# Logic_Port.net
KiCad netlist of a schematic drawn in Altium Designer
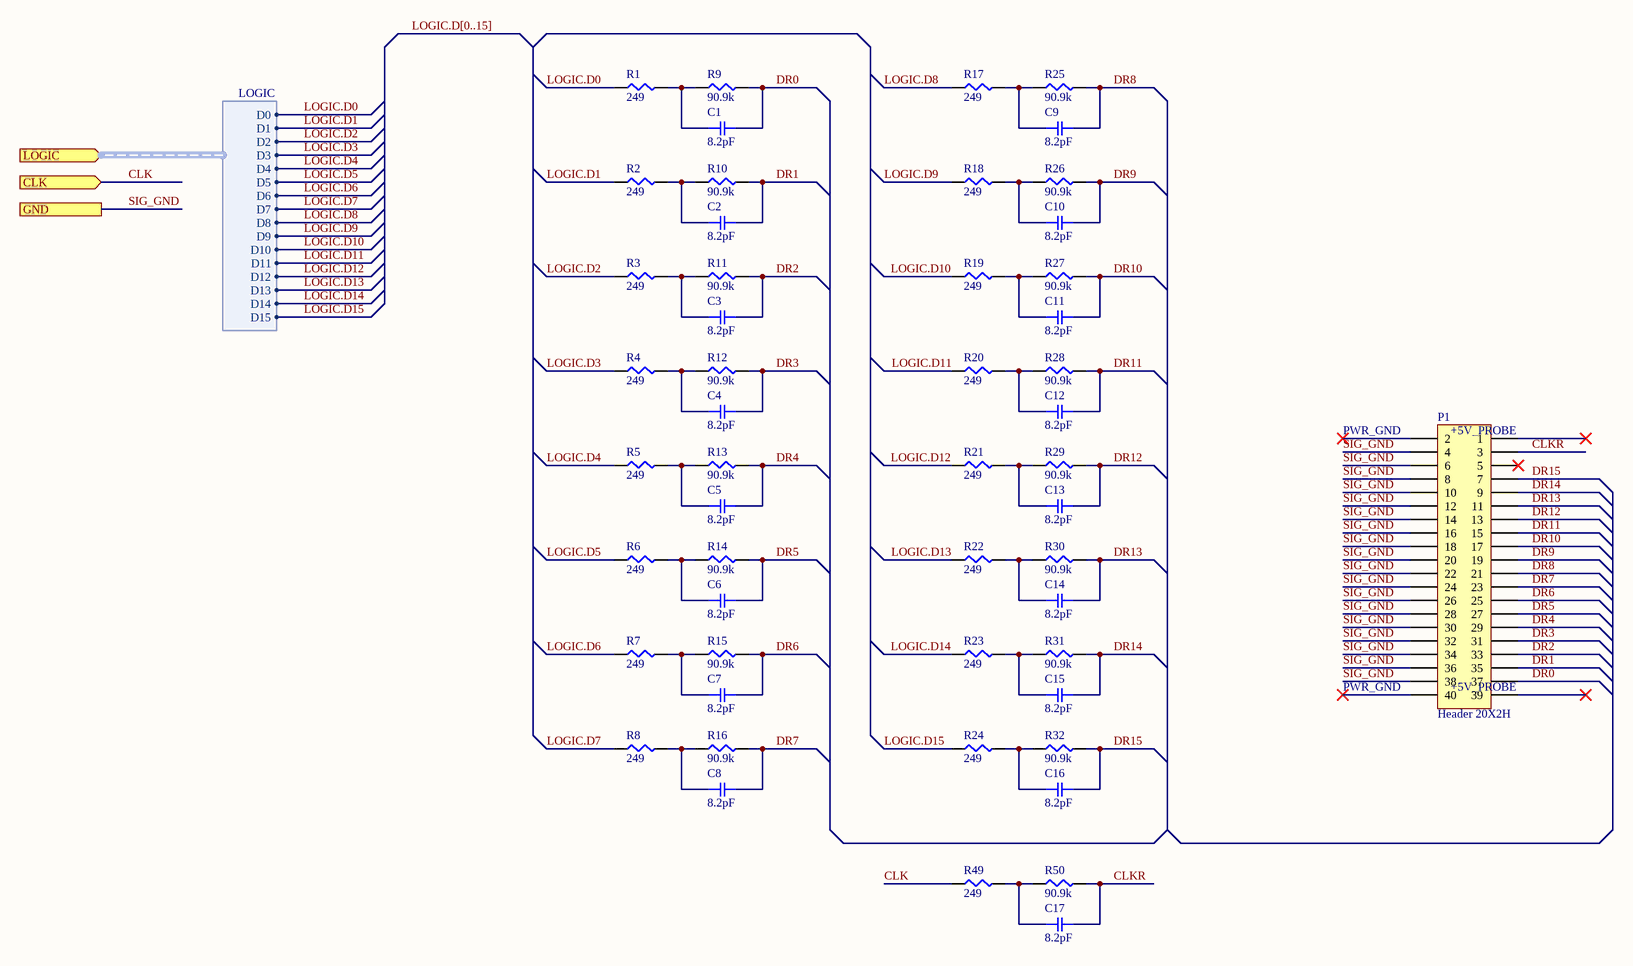
[diagram p0: Logic Port.SchDoc]

(export (version "E")
  (design (tool "Eeschema 10.0.6"))
  (components
    (comp (ref "C1")
      (value "8.2pF")
      (footprint "SMD-0603C")
      (description "CAP CER 8.2PF 50V NP0 0603")
      (fields
        (field (name "DIGI-KEY PART NUMBER") "490-12727-1-ND")
        (field (name "PART NUMBER") "GRM1885C1H8R2BA01D")
      )
      (libsource (lib "capacitor_murata_0603") (part "GRM1885C1H8R2BA01D"))
    )
    (comp (ref "C2")
      (value "8.2pF")
      (footprint "SMD-0603C")
      (description "CAP CER 8.2PF 50V NP0 0603")
      (fields
        (field (name "DIGI-KEY PART NUMBER") "490-12727-1-ND")
        (field (name "PART NUMBER") "GRM1885C1H8R2BA01D")
      )
      (libsource (lib "capacitor_murata_0603") (part "GRM1885C1H8R2BA01D"))
    )
    (comp (ref "C3")
      (value "8.2pF")
      (footprint "SMD-0603C")
      (description "CAP CER 8.2PF 50V NP0 0603")
      (fields
        (field (name "DIGI-KEY PART NUMBER") "490-12727-1-ND")
        (field (name "PART NUMBER") "GRM1885C1H8R2BA01D")
      )
      (libsource (lib "capacitor_murata_0603") (part "GRM1885C1H8R2BA01D"))
    )
    (comp (ref "C4")
      (value "8.2pF")
      (footprint "SMD-0603C")
      (description "CAP CER 8.2PF 50V NP0 0603")
      (fields
        (field (name "DIGI-KEY PART NUMBER") "490-12727-1-ND")
        (field (name "PART NUMBER") "GRM1885C1H8R2BA01D")
      )
      (libsource (lib "capacitor_murata_0603") (part "GRM1885C1H8R2BA01D"))
    )
    (comp (ref "C5")
      (value "8.2pF")
      (footprint "SMD-0603C")
      (description "CAP CER 8.2PF 50V NP0 0603")
      (fields
        (field (name "DIGI-KEY PART NUMBER") "490-12727-1-ND")
        (field (name "PART NUMBER") "GRM1885C1H8R2BA01D")
      )
      (libsource (lib "capacitor_murata_0603") (part "GRM1885C1H8R2BA01D"))
    )
    (comp (ref "C6")
      (value "8.2pF")
      (footprint "SMD-0603C")
      (description "CAP CER 8.2PF 50V NP0 0603")
      (fields
        (field (name "DIGI-KEY PART NUMBER") "490-12727-1-ND")
        (field (name "PART NUMBER") "GRM1885C1H8R2BA01D")
      )
      (libsource (lib "capacitor_murata_0603") (part "GRM1885C1H8R2BA01D"))
    )
    (comp (ref "C7")
      (value "8.2pF")
      (footprint "SMD-0603C")
      (description "CAP CER 8.2PF 50V NP0 0603")
      (fields
        (field (name "DIGI-KEY PART NUMBER") "490-12727-1-ND")
        (field (name "PART NUMBER") "GRM1885C1H8R2BA01D")
      )
      (libsource (lib "capacitor_murata_0603") (part "GRM1885C1H8R2BA01D"))
    )
    (comp (ref "C8")
      (value "8.2pF")
      (footprint "SMD-0603C")
      (description "CAP CER 8.2PF 50V NP0 0603")
      (fields
        (field (name "DIGI-KEY PART NUMBER") "490-12727-1-ND")
        (field (name "PART NUMBER") "GRM1885C1H8R2BA01D")
      )
      (libsource (lib "capacitor_murata_0603") (part "GRM1885C1H8R2BA01D"))
    )
    (comp (ref "C9")
      (value "8.2pF")
      (footprint "SMD-0603C")
      (description "CAP CER 8.2PF 50V NP0 0603")
      (fields
        (field (name "DIGI-KEY PART NUMBER") "490-12727-1-ND")
        (field (name "PART NUMBER") "GRM1885C1H8R2BA01D")
      )
      (libsource (lib "capacitor_murata_0603") (part "GRM1885C1H8R2BA01D"))
    )
    (comp (ref "C10")
      (value "8.2pF")
      (footprint "SMD-0603C")
      (description "CAP CER 8.2PF 50V NP0 0603")
      (fields
        (field (name "DIGI-KEY PART NUMBER") "490-12727-1-ND")
        (field (name "PART NUMBER") "GRM1885C1H8R2BA01D")
      )
      (libsource (lib "capacitor_murata_0603") (part "GRM1885C1H8R2BA01D"))
    )
    (comp (ref "C11")
      (value "8.2pF")
      (footprint "SMD-0603C")
      (description "CAP CER 8.2PF 50V NP0 0603")
      (fields
        (field (name "DIGI-KEY PART NUMBER") "490-12727-1-ND")
        (field (name "PART NUMBER") "GRM1885C1H8R2BA01D")
      )
      (libsource (lib "capacitor_murata_0603") (part "GRM1885C1H8R2BA01D"))
    )
    (comp (ref "C12")
      (value "8.2pF")
      (footprint "SMD-0603C")
      (description "CAP CER 8.2PF 50V NP0 0603")
      (fields
        (field (name "DIGI-KEY PART NUMBER") "490-12727-1-ND")
        (field (name "PART NUMBER") "GRM1885C1H8R2BA01D")
      )
      (libsource (lib "capacitor_murata_0603") (part "GRM1885C1H8R2BA01D"))
    )
    (comp (ref "C13")
      (value "8.2pF")
      (footprint "SMD-0603C")
      (description "CAP CER 8.2PF 50V NP0 0603")
      (fields
        (field (name "DIGI-KEY PART NUMBER") "490-12727-1-ND")
        (field (name "PART NUMBER") "GRM1885C1H8R2BA01D")
      )
      (libsource (lib "capacitor_murata_0603") (part "GRM1885C1H8R2BA01D"))
    )
    (comp (ref "C14")
      (value "8.2pF")
      (footprint "SMD-0603C")
      (description "CAP CER 8.2PF 50V NP0 0603")
      (fields
        (field (name "DIGI-KEY PART NUMBER") "490-12727-1-ND")
        (field (name "PART NUMBER") "GRM1885C1H8R2BA01D")
      )
      (libsource (lib "capacitor_murata_0603") (part "GRM1885C1H8R2BA01D"))
    )
    (comp (ref "C15")
      (value "8.2pF")
      (footprint "SMD-0603C")
      (description "CAP CER 8.2PF 50V NP0 0603")
      (fields
        (field (name "DIGI-KEY PART NUMBER") "490-12727-1-ND")
        (field (name "PART NUMBER") "GRM1885C1H8R2BA01D")
      )
      (libsource (lib "capacitor_murata_0603") (part "GRM1885C1H8R2BA01D"))
    )
    (comp (ref "C16")
      (value "8.2pF")
      (footprint "SMD-0603C")
      (description "CAP CER 8.2PF 50V NP0 0603")
      (fields
        (field (name "DIGI-KEY PART NUMBER") "490-12727-1-ND")
        (field (name "PART NUMBER") "GRM1885C1H8R2BA01D")
      )
      (libsource (lib "capacitor_murata_0603") (part "GRM1885C1H8R2BA01D"))
    )
    (comp (ref "C17")
      (value "8.2pF")
      (footprint "SMD-0603C")
      (description "CAP CER 8.2PF 50V NP0 0603")
      (fields
        (field (name "DIGI-KEY PART NUMBER") "490-12727-1-ND")
        (field (name "PART NUMBER") "GRM1885C1H8R2BA01D")
      )
      (libsource (lib "capacitor_murata_0603") (part "GRM1885C1H8R2BA01D"))
    )
    (comp (ref "P1")
      (value "Header 20X2H")
      (footprint "HDR2X20H")
      (description "Header, 20-Pin, Dual row, Right Angle")
      (fields (field (name "PUBLISHER") "Altium Limited"))
      (libsource (lib "Miscellaneous Connectors") (part "Header 20X2H"))
    )
    (comp (ref "R1")
      (value "249")
      (footprint "SMD-0603-RES")
      (description "RES SMD 249 OHM 1% 1/10W 0603")
      (fields (field (name "PART NUMBER") "ERJ-3EKF2490V") (field (name "DIGI-KEY PART NUMBER") "P249HCT-ND"))
      (libsource (lib "Panasonic_ERJ_0603") (part "ERJ-3EKF2490V"))
    )
    (comp (ref "R2")
      (value "249")
      (footprint "SMD-0603-RES")
      (description "RES SMD 249 OHM 1% 1/10W 0603")
      (fields (field (name "PART NUMBER") "ERJ-3EKF2490V") (field (name "DIGI-KEY PART NUMBER") "P249HCT-ND"))
      (libsource (lib "Panasonic_ERJ_0603") (part "ERJ-3EKF2490V"))
    )
    (comp (ref "R3")
      (value "249")
      (footprint "SMD-0603-RES")
      (description "RES SMD 249 OHM 1% 1/10W 0603")
      (fields (field (name "PART NUMBER") "ERJ-3EKF2490V") (field (name "DIGI-KEY PART NUMBER") "P249HCT-ND"))
      (libsource (lib "Panasonic_ERJ_0603") (part "ERJ-3EKF2490V"))
    )
    (comp (ref "R4")
      (value "249")
      (footprint "SMD-0603-RES")
      (description "RES SMD 249 OHM 1% 1/10W 0603")
      (fields (field (name "PART NUMBER") "ERJ-3EKF2490V") (field (name "DIGI-KEY PART NUMBER") "P249HCT-ND"))
      (libsource (lib "Panasonic_ERJ_0603") (part "ERJ-3EKF2490V"))
    )
    (comp (ref "R5")
      (value "249")
      (footprint "SMD-0603-RES")
      (description "RES SMD 249 OHM 1% 1/10W 0603")
      (fields (field (name "PART NUMBER") "ERJ-3EKF2490V") (field (name "DIGI-KEY PART NUMBER") "P249HCT-ND"))
      (libsource (lib "Panasonic_ERJ_0603") (part "ERJ-3EKF2490V"))
    )
    (comp (ref "R6")
      (value "249")
      (footprint "SMD-0603-RES")
      (description "RES SMD 249 OHM 1% 1/10W 0603")
      (fields (field (name "PART NUMBER") "ERJ-3EKF2490V") (field (name "DIGI-KEY PART NUMBER") "P249HCT-ND"))
      (libsource (lib "Panasonic_ERJ_0603") (part "ERJ-3EKF2490V"))
    )
    (comp (ref "R7")
      (value "249")
      (footprint "SMD-0603-RES")
      (description "RES SMD 249 OHM 1% 1/10W 0603")
      (fields (field (name "PART NUMBER") "ERJ-3EKF2490V") (field (name "DIGI-KEY PART NUMBER") "P249HCT-ND"))
      (libsource (lib "Panasonic_ERJ_0603") (part "ERJ-3EKF2490V"))
    )
    (comp (ref "R8")
      (value "249")
      (footprint "SMD-0603-RES")
      (description "RES SMD 249 OHM 1% 1/10W 0603")
      (fields (field (name "PART NUMBER") "ERJ-3EKF2490V") (field (name "DIGI-KEY PART NUMBER") "P249HCT-ND"))
      (libsource (lib "Panasonic_ERJ_0603") (part "ERJ-3EKF2490V"))
    )
    (comp (ref "R9")
      (value "90.9k")
      (footprint "SMD-0603-RES")
      (description "RES SMD 90.9K OHM 1% 1/10W 0603")
      (fields
        (field (name "PART NUMBER") "ERJ-3EKF9092V")
        (field (name "DIGI-KEY PART NUMBER") "P90.9KHCT-ND")
      )
      (libsource (lib "Panasonic_ERJ_0603") (part "ERJ-3EKF9092V"))
    )
    (comp (ref "R10")
      (value "90.9k")
      (footprint "SMD-0603-RES")
      (description "RES SMD 90.9K OHM 1% 1/10W 0603")
      (fields
        (field (name "PART NUMBER") "ERJ-3EKF9092V")
        (field (name "DIGI-KEY PART NUMBER") "P90.9KHCT-ND")
      )
      (libsource (lib "Panasonic_ERJ_0603") (part "ERJ-3EKF9092V"))
    )
    (comp (ref "R11")
      (value "90.9k")
      (footprint "SMD-0603-RES")
      (description "RES SMD 90.9K OHM 1% 1/10W 0603")
      (fields
        (field (name "PART NUMBER") "ERJ-3EKF9092V")
        (field (name "DIGI-KEY PART NUMBER") "P90.9KHCT-ND")
      )
      (libsource (lib "Panasonic_ERJ_0603") (part "ERJ-3EKF9092V"))
    )
    (comp (ref "R12")
      (value "90.9k")
      (footprint "SMD-0603-RES")
      (description "RES SMD 90.9K OHM 1% 1/10W 0603")
      (fields
        (field (name "PART NUMBER") "ERJ-3EKF9092V")
        (field (name "DIGI-KEY PART NUMBER") "P90.9KHCT-ND")
      )
      (libsource (lib "Panasonic_ERJ_0603") (part "ERJ-3EKF9092V"))
    )
    (comp (ref "R13")
      (value "90.9k")
      (footprint "SMD-0603-RES")
      (description "RES SMD 90.9K OHM 1% 1/10W 0603")
      (fields
        (field (name "PART NUMBER") "ERJ-3EKF9092V")
        (field (name "DIGI-KEY PART NUMBER") "P90.9KHCT-ND")
      )
      (libsource (lib "Panasonic_ERJ_0603") (part "ERJ-3EKF9092V"))
    )
    (comp (ref "R14")
      (value "90.9k")
      (footprint "SMD-0603-RES")
      (description "RES SMD 90.9K OHM 1% 1/10W 0603")
      (fields
        (field (name "PART NUMBER") "ERJ-3EKF9092V")
        (field (name "DIGI-KEY PART NUMBER") "P90.9KHCT-ND")
      )
      (libsource (lib "Panasonic_ERJ_0603") (part "ERJ-3EKF9092V"))
    )
    (comp (ref "R15")
      (value "90.9k")
      (footprint "SMD-0603-RES")
      (description "RES SMD 90.9K OHM 1% 1/10W 0603")
      (fields
        (field (name "PART NUMBER") "ERJ-3EKF9092V")
        (field (name "DIGI-KEY PART NUMBER") "P90.9KHCT-ND")
      )
      (libsource (lib "Panasonic_ERJ_0603") (part "ERJ-3EKF9092V"))
    )
    (comp (ref "R16")
      (value "90.9k")
      (footprint "SMD-0603-RES")
      (description "RES SMD 90.9K OHM 1% 1/10W 0603")
      (fields
        (field (name "PART NUMBER") "ERJ-3EKF9092V")
        (field (name "DIGI-KEY PART NUMBER") "P90.9KHCT-ND")
      )
      (libsource (lib "Panasonic_ERJ_0603") (part "ERJ-3EKF9092V"))
    )
    (comp (ref "R17")
      (value "249")
      (footprint "SMD-0603-RES")
      (description "RES SMD 249 OHM 1% 1/10W 0603")
      (fields (field (name "PART NUMBER") "ERJ-3EKF2490V") (field (name "DIGI-KEY PART NUMBER") "P249HCT-ND"))
      (libsource (lib "Panasonic_ERJ_0603") (part "ERJ-3EKF2490V"))
    )
    (comp (ref "R18")
      (value "249")
      (footprint "SMD-0603-RES")
      (description "RES SMD 249 OHM 1% 1/10W 0603")
      (fields (field (name "PART NUMBER") "ERJ-3EKF2490V") (field (name "DIGI-KEY PART NUMBER") "P249HCT-ND"))
      (libsource (lib "Panasonic_ERJ_0603") (part "ERJ-3EKF2490V"))
    )
    (comp (ref "R19")
      (value "249")
      (footprint "SMD-0603-RES")
      (description "RES SMD 249 OHM 1% 1/10W 0603")
      (fields (field (name "PART NUMBER") "ERJ-3EKF2490V") (field (name "DIGI-KEY PART NUMBER") "P249HCT-ND"))
      (libsource (lib "Panasonic_ERJ_0603") (part "ERJ-3EKF2490V"))
    )
    (comp (ref "R20")
      (value "249")
      (footprint "SMD-0603-RES")
      (description "RES SMD 249 OHM 1% 1/10W 0603")
      (fields (field (name "PART NUMBER") "ERJ-3EKF2490V") (field (name "DIGI-KEY PART NUMBER") "P249HCT-ND"))
      (libsource (lib "Panasonic_ERJ_0603") (part "ERJ-3EKF2490V"))
    )
    (comp (ref "R21")
      (value "249")
      (footprint "SMD-0603-RES")
      (description "RES SMD 249 OHM 1% 1/10W 0603")
      (fields (field (name "PART NUMBER") "ERJ-3EKF2490V") (field (name "DIGI-KEY PART NUMBER") "P249HCT-ND"))
      (libsource (lib "Panasonic_ERJ_0603") (part "ERJ-3EKF2490V"))
    )
    (comp (ref "R22")
      (value "249")
      (footprint "SMD-0603-RES")
      (description "RES SMD 249 OHM 1% 1/10W 0603")
      (fields (field (name "PART NUMBER") "ERJ-3EKF2490V") (field (name "DIGI-KEY PART NUMBER") "P249HCT-ND"))
      (libsource (lib "Panasonic_ERJ_0603") (part "ERJ-3EKF2490V"))
    )
    (comp (ref "R23")
      (value "249")
      (footprint "SMD-0603-RES")
      (description "RES SMD 249 OHM 1% 1/10W 0603")
      (fields (field (name "PART NUMBER") "ERJ-3EKF2490V") (field (name "DIGI-KEY PART NUMBER") "P249HCT-ND"))
      (libsource (lib "Panasonic_ERJ_0603") (part "ERJ-3EKF2490V"))
    )
    (comp (ref "R24")
      (value "249")
      (footprint "SMD-0603-RES")
      (description "RES SMD 249 OHM 1% 1/10W 0603")
      (fields (field (name "PART NUMBER") "ERJ-3EKF2490V") (field (name "DIGI-KEY PART NUMBER") "P249HCT-ND"))
      (libsource (lib "Panasonic_ERJ_0603") (part "ERJ-3EKF2490V"))
    )
    (comp (ref "R25")
      (value "90.9k")
      (footprint "SMD-0603-RES")
      (description "RES SMD 90.9K OHM 1% 1/10W 0603")
      (fields
        (field (name "PART NUMBER") "ERJ-3EKF9092V")
        (field (name "DIGI-KEY PART NUMBER") "P90.9KHCT-ND")
      )
      (libsource (lib "Panasonic_ERJ_0603") (part "ERJ-3EKF9092V"))
    )
    (comp (ref "R26")
      (value "90.9k")
      (footprint "SMD-0603-RES")
      (description "RES SMD 90.9K OHM 1% 1/10W 0603")
      (fields
        (field (name "PART NUMBER") "ERJ-3EKF9092V")
        (field (name "DIGI-KEY PART NUMBER") "P90.9KHCT-ND")
      )
      (libsource (lib "Panasonic_ERJ_0603") (part "ERJ-3EKF9092V"))
    )
    (comp (ref "R27")
      (value "90.9k")
      (footprint "SMD-0603-RES")
      (description "RES SMD 90.9K OHM 1% 1/10W 0603")
      (fields
        (field (name "PART NUMBER") "ERJ-3EKF9092V")
        (field (name "DIGI-KEY PART NUMBER") "P90.9KHCT-ND")
      )
      (libsource (lib "Panasonic_ERJ_0603") (part "ERJ-3EKF9092V"))
    )
    (comp (ref "R28")
      (value "90.9k")
      (footprint "SMD-0603-RES")
      (description "RES SMD 90.9K OHM 1% 1/10W 0603")
      (fields
        (field (name "PART NUMBER") "ERJ-3EKF9092V")
        (field (name "DIGI-KEY PART NUMBER") "P90.9KHCT-ND")
      )
      (libsource (lib "Panasonic_ERJ_0603") (part "ERJ-3EKF9092V"))
    )
    (comp (ref "R29")
      (value "90.9k")
      (footprint "SMD-0603-RES")
      (description "RES SMD 90.9K OHM 1% 1/10W 0603")
      (fields
        (field (name "PART NUMBER") "ERJ-3EKF9092V")
        (field (name "DIGI-KEY PART NUMBER") "P90.9KHCT-ND")
      )
      (libsource (lib "Panasonic_ERJ_0603") (part "ERJ-3EKF9092V"))
    )
    (comp (ref "R30")
      (value "90.9k")
      (footprint "SMD-0603-RES")
      (description "RES SMD 90.9K OHM 1% 1/10W 0603")
      (fields
        (field (name "PART NUMBER") "ERJ-3EKF9092V")
        (field (name "DIGI-KEY PART NUMBER") "P90.9KHCT-ND")
      )
      (libsource (lib "Panasonic_ERJ_0603") (part "ERJ-3EKF9092V"))
    )
    (comp (ref "R31")
      (value "90.9k")
      (footprint "SMD-0603-RES")
      (description "RES SMD 90.9K OHM 1% 1/10W 0603")
      (fields
        (field (name "PART NUMBER") "ERJ-3EKF9092V")
        (field (name "DIGI-KEY PART NUMBER") "P90.9KHCT-ND")
      )
      (libsource (lib "Panasonic_ERJ_0603") (part "ERJ-3EKF9092V"))
    )
    (comp (ref "R32")
      (value "90.9k")
      (footprint "SMD-0603-RES")
      (description "RES SMD 90.9K OHM 1% 1/10W 0603")
      (fields
        (field (name "PART NUMBER") "ERJ-3EKF9092V")
        (field (name "DIGI-KEY PART NUMBER") "P90.9KHCT-ND")
      )
      (libsource (lib "Panasonic_ERJ_0603") (part "ERJ-3EKF9092V"))
    )
    (comp (ref "R49")
      (value "249")
      (footprint "SMD-0603-RES")
      (description "RES SMD 249 OHM 1% 1/10W 0603")
      (fields (field (name "PART NUMBER") "ERJ-3EKF2490V") (field (name "DIGI-KEY PART NUMBER") "P249HCT-ND"))
      (libsource (lib "Panasonic_ERJ_0603") (part "ERJ-3EKF2490V"))
    )
    (comp (ref "R50")
      (value "90.9k")
      (footprint "SMD-0603-RES")
      (description "RES SMD 90.9K OHM 1% 1/10W 0603")
      (fields
        (field (name "PART NUMBER") "ERJ-3EKF9092V")
        (field (name "DIGI-KEY PART NUMBER") "P90.9KHCT-ND")
      )
      (libsource (lib "Panasonic_ERJ_0603") (part "ERJ-3EKF9092V"))
    )
  )
  (nets
    (net (code "2") (name "/CLK") (class "Default")
      (node (ref "R49") (pin "1") (pinfunction "1_1") (pintype "passive"))
    )
    (net (code "3") (name "/CLKR") (class "Default")
      (node (ref "C17") (pin "2") (pinfunction "2_2") (pintype "passive"))
      (node (ref "P1") (pin "3") (pinfunction "3_3") (pintype "passive"))
      (node (ref "R50") (pin "2") (pinfunction "2_2") (pintype "passive"))
    )
    (net (code "4") (name "/DR0") (class "Default")
      (node (ref "C1") (pin "2") (pinfunction "2_2") (pintype "passive"))
      (node (ref "P1") (pin "37") (pinfunction "37_37") (pintype "passive"))
      (node (ref "R9") (pin "2") (pinfunction "2_2") (pintype "passive"))
    )
    (net (code "5") (name "/DR1") (class "Default")
      (node (ref "C2") (pin "2") (pinfunction "2_2") (pintype "passive"))
      (node (ref "P1") (pin "35") (pinfunction "35_35") (pintype "passive"))
      (node (ref "R10") (pin "2") (pinfunction "2_2") (pintype "passive"))
    )
    (net (code "6") (name "/DR2") (class "Default")
      (node (ref "C3") (pin "2") (pinfunction "2_2") (pintype "passive"))
      (node (ref "P1") (pin "33") (pinfunction "33_33") (pintype "passive"))
      (node (ref "R11") (pin "2") (pinfunction "2_2") (pintype "passive"))
    )
    (net (code "7") (name "/DR3") (class "Default")
      (node (ref "C4") (pin "2") (pinfunction "2_2") (pintype "passive"))
      (node (ref "P1") (pin "31") (pinfunction "31_31") (pintype "passive"))
      (node (ref "R12") (pin "2") (pinfunction "2_2") (pintype "passive"))
    )
    (net (code "8") (name "/DR4") (class "Default")
      (node (ref "C5") (pin "2") (pinfunction "2_2") (pintype "passive"))
      (node (ref "P1") (pin "29") (pinfunction "29_29") (pintype "passive"))
      (node (ref "R13") (pin "2") (pinfunction "2_2") (pintype "passive"))
    )
    (net (code "9") (name "/DR5") (class "Default")
      (node (ref "C6") (pin "2") (pinfunction "2_2") (pintype "passive"))
      (node (ref "P1") (pin "27") (pinfunction "27_27") (pintype "passive"))
      (node (ref "R14") (pin "2") (pinfunction "2_2") (pintype "passive"))
    )
    (net (code "10") (name "/DR6") (class "Default")
      (node (ref "C7") (pin "2") (pinfunction "2_2") (pintype "passive"))
      (node (ref "P1") (pin "25") (pinfunction "25_25") (pintype "passive"))
      (node (ref "R15") (pin "2") (pinfunction "2_2") (pintype "passive"))
    )
    (net (code "11") (name "/DR7") (class "Default")
      (node (ref "C8") (pin "2") (pinfunction "2_2") (pintype "passive"))
      (node (ref "P1") (pin "23") (pinfunction "23_23") (pintype "passive"))
      (node (ref "R16") (pin "2") (pinfunction "2_2") (pintype "passive"))
    )
    (net (code "12") (name "/DR8") (class "Default")
      (node (ref "C9") (pin "2") (pinfunction "2_2") (pintype "passive"))
      (node (ref "P1") (pin "21") (pinfunction "21_21") (pintype "passive"))
      (node (ref "R25") (pin "2") (pinfunction "2_2") (pintype "passive"))
    )
    (net (code "13") (name "/DR9") (class "Default")
      (node (ref "C10") (pin "2") (pinfunction "2_2") (pintype "passive"))
      (node (ref "P1") (pin "19") (pinfunction "19_19") (pintype "passive"))
      (node (ref "R26") (pin "2") (pinfunction "2_2") (pintype "passive"))
    )
    (net (code "14") (name "/DR10") (class "Default")
      (node (ref "C11") (pin "2") (pinfunction "2_2") (pintype "passive"))
      (node (ref "P1") (pin "17") (pinfunction "17_17") (pintype "passive"))
      (node (ref "R27") (pin "2") (pinfunction "2_2") (pintype "passive"))
    )
    (net (code "15") (name "/DR11") (class "Default")
      (node (ref "C12") (pin "2") (pinfunction "2_2") (pintype "passive"))
      (node (ref "P1") (pin "15") (pinfunction "15_15") (pintype "passive"))
      (node (ref "R28") (pin "2") (pinfunction "2_2") (pintype "passive"))
    )
    (net (code "16") (name "/DR12") (class "Default")
      (node (ref "C13") (pin "2") (pinfunction "2_2") (pintype "passive"))
      (node (ref "P1") (pin "13") (pinfunction "13_13") (pintype "passive"))
      (node (ref "R29") (pin "2") (pinfunction "2_2") (pintype "passive"))
    )
    (net (code "17") (name "/DR13") (class "Default")
      (node (ref "C14") (pin "2") (pinfunction "2_2") (pintype "passive"))
      (node (ref "P1") (pin "11") (pinfunction "11_11") (pintype "passive"))
      (node (ref "R30") (pin "2") (pinfunction "2_2") (pintype "passive"))
    )
    (net (code "18") (name "/DR14") (class "Default")
      (node (ref "C15") (pin "2") (pinfunction "2_2") (pintype "passive"))
      (node (ref "P1") (pin "9") (pinfunction "9_9") (pintype "passive"))
      (node (ref "R31") (pin "2") (pinfunction "2_2") (pintype "passive"))
    )
    (net (code "19") (name "/DR15") (class "Default")
      (node (ref "C16") (pin "2") (pinfunction "2_2") (pintype "passive"))
      (node (ref "P1") (pin "7") (pinfunction "7_7") (pintype "passive"))
      (node (ref "R32") (pin "2") (pinfunction "2_2") (pintype "passive"))
    )
    (net (code "20") (name "/LOGIC.D0") (class "Default")
      (node (ref "R1") (pin "1") (pinfunction "1_1") (pintype "passive"))
    )
    (net (code "21") (name "/LOGIC.D1") (class "Default")
      (node (ref "R2") (pin "1") (pinfunction "1_1") (pintype "passive"))
    )
    (net (code "22") (name "/LOGIC.D2") (class "Default")
      (node (ref "R3") (pin "1") (pinfunction "1_1") (pintype "passive"))
    )
    (net (code "23") (name "/LOGIC.D3") (class "Default")
      (node (ref "R4") (pin "1") (pinfunction "1_1") (pintype "passive"))
    )
    (net (code "24") (name "/LOGIC.D4") (class "Default")
      (node (ref "R5") (pin "1") (pinfunction "1_1") (pintype "passive"))
    )
    (net (code "25") (name "/LOGIC.D5") (class "Default")
      (node (ref "R6") (pin "1") (pinfunction "1_1") (pintype "passive"))
    )
    (net (code "26") (name "/LOGIC.D6") (class "Default")
      (node (ref "R7") (pin "1") (pinfunction "1_1") (pintype "passive"))
    )
    (net (code "27") (name "/LOGIC.D7") (class "Default")
      (node (ref "R8") (pin "1") (pinfunction "1_1") (pintype "passive"))
    )
    (net (code "28") (name "/LOGIC.D8") (class "Default")
      (node (ref "R17") (pin "1") (pinfunction "1_1") (pintype "passive"))
    )
    (net (code "29") (name "/LOGIC.D9") (class "Default")
      (node (ref "R18") (pin "1") (pinfunction "1_1") (pintype "passive"))
    )
    (net (code "30") (name "/LOGIC.D10") (class "Default")
      (node (ref "R19") (pin "1") (pinfunction "1_1") (pintype "passive"))
    )
    (net (code "31") (name "/LOGIC.D11") (class "Default")
      (node (ref "R20") (pin "1") (pinfunction "1_1") (pintype "passive"))
    )
    (net (code "32") (name "/LOGIC.D12") (class "Default")
      (node (ref "R21") (pin "1") (pinfunction "1_1") (pintype "passive"))
    )
    (net (code "33") (name "/LOGIC.D13") (class "Default")
      (node (ref "R22") (pin "1") (pinfunction "1_1") (pintype "passive"))
    )
    (net (code "34") (name "/LOGIC.D14") (class "Default")
      (node (ref "R23") (pin "1") (pinfunction "1_1") (pintype "passive"))
    )
    (net (code "35") (name "/LOGIC.D15") (class "Default")
      (node (ref "R24") (pin "1") (pinfunction "1_1") (pintype "passive"))
    )
    (net (code "37") (name "/SIG_GND") (class "Default")
      (node (ref "P1") (pin "10") (pinfunction "10_10") (pintype "passive"))
      (node (ref "P1") (pin "12") (pinfunction "12_12") (pintype "passive"))
      (node (ref "P1") (pin "14") (pinfunction "14_14") (pintype "passive"))
      (node (ref "P1") (pin "16") (pinfunction "16_16") (pintype "passive"))
      (node (ref "P1") (pin "18") (pinfunction "18_18") (pintype "passive"))
      (node (ref "P1") (pin "20") (pinfunction "20_20") (pintype "passive"))
      (node (ref "P1") (pin "22") (pinfunction "22_22") (pintype "passive"))
      (node (ref "P1") (pin "24") (pinfunction "24_24") (pintype "passive"))
      (node (ref "P1") (pin "26") (pinfunction "26_26") (pintype "passive"))
      (node (ref "P1") (pin "28") (pinfunction "28_28") (pintype "passive"))
      (node (ref "P1") (pin "30") (pinfunction "30_30") (pintype "passive"))
      (node (ref "P1") (pin "32") (pinfunction "32_32") (pintype "passive"))
      (node (ref "P1") (pin "34") (pinfunction "34_34") (pintype "passive"))
      (node (ref "P1") (pin "36") (pinfunction "36_36") (pintype "passive"))
      (node (ref "P1") (pin "38") (pinfunction "38_38") (pintype "passive"))
      (node (ref "P1") (pin "4") (pinfunction "4_4") (pintype "passive"))
      (node (ref "P1") (pin "6") (pinfunction "6_6") (pintype "passive"))
      (node (ref "P1") (pin "8") (pinfunction "8_8") (pintype "passive"))
    )
    (net (code "39") (name "Net-(C1-Pad1)") (class "Default")
      (node (ref "C1") (pin "1") (pinfunction "1_1") (pintype "passive"))
      (node (ref "R1") (pin "2") (pinfunction "2_2") (pintype "passive"))
      (node (ref "R9") (pin "1") (pinfunction "1_1") (pintype "passive"))
    )
    (net (code "40") (name "Net-(C2-Pad1)") (class "Default")
      (node (ref "C2") (pin "1") (pinfunction "1_1") (pintype "passive"))
      (node (ref "R10") (pin "1") (pinfunction "1_1") (pintype "passive"))
      (node (ref "R2") (pin "2") (pinfunction "2_2") (pintype "passive"))
    )
    (net (code "41") (name "Net-(C3-Pad1)") (class "Default")
      (node (ref "C3") (pin "1") (pinfunction "1_1") (pintype "passive"))
      (node (ref "R11") (pin "1") (pinfunction "1_1") (pintype "passive"))
      (node (ref "R3") (pin "2") (pinfunction "2_2") (pintype "passive"))
    )
    (net (code "42") (name "Net-(C4-Pad1)") (class "Default")
      (node (ref "C4") (pin "1") (pinfunction "1_1") (pintype "passive"))
      (node (ref "R12") (pin "1") (pinfunction "1_1") (pintype "passive"))
      (node (ref "R4") (pin "2") (pinfunction "2_2") (pintype "passive"))
    )
    (net (code "43") (name "Net-(C5-Pad1)") (class "Default")
      (node (ref "C5") (pin "1") (pinfunction "1_1") (pintype "passive"))
      (node (ref "R13") (pin "1") (pinfunction "1_1") (pintype "passive"))
      (node (ref "R5") (pin "2") (pinfunction "2_2") (pintype "passive"))
    )
    (net (code "44") (name "Net-(C6-Pad1)") (class "Default")
      (node (ref "C6") (pin "1") (pinfunction "1_1") (pintype "passive"))
      (node (ref "R14") (pin "1") (pinfunction "1_1") (pintype "passive"))
      (node (ref "R6") (pin "2") (pinfunction "2_2") (pintype "passive"))
    )
    (net (code "45") (name "Net-(C7-Pad1)") (class "Default")
      (node (ref "C7") (pin "1") (pinfunction "1_1") (pintype "passive"))
      (node (ref "R15") (pin "1") (pinfunction "1_1") (pintype "passive"))
      (node (ref "R7") (pin "2") (pinfunction "2_2") (pintype "passive"))
    )
    (net (code "46") (name "Net-(C8-Pad1)") (class "Default")
      (node (ref "C8") (pin "1") (pinfunction "1_1") (pintype "passive"))
      (node (ref "R16") (pin "1") (pinfunction "1_1") (pintype "passive"))
      (node (ref "R8") (pin "2") (pinfunction "2_2") (pintype "passive"))
    )
    (net (code "47") (name "Net-(C9-Pad1)") (class "Default")
      (node (ref "C9") (pin "1") (pinfunction "1_1") (pintype "passive"))
      (node (ref "R17") (pin "2") (pinfunction "2_2") (pintype "passive"))
      (node (ref "R25") (pin "1") (pinfunction "1_1") (pintype "passive"))
    )
    (net (code "48") (name "Net-(C10-Pad1)") (class "Default")
      (node (ref "C10") (pin "1") (pinfunction "1_1") (pintype "passive"))
      (node (ref "R18") (pin "2") (pinfunction "2_2") (pintype "passive"))
      (node (ref "R26") (pin "1") (pinfunction "1_1") (pintype "passive"))
    )
    (net (code "49") (name "Net-(C11-Pad1)") (class "Default")
      (node (ref "C11") (pin "1") (pinfunction "1_1") (pintype "passive"))
      (node (ref "R19") (pin "2") (pinfunction "2_2") (pintype "passive"))
      (node (ref "R27") (pin "1") (pinfunction "1_1") (pintype "passive"))
    )
    (net (code "50") (name "Net-(C12-Pad1)") (class "Default")
      (node (ref "C12") (pin "1") (pinfunction "1_1") (pintype "passive"))
      (node (ref "R20") (pin "2") (pinfunction "2_2") (pintype "passive"))
      (node (ref "R28") (pin "1") (pinfunction "1_1") (pintype "passive"))
    )
    (net (code "51") (name "Net-(C13-Pad1)") (class "Default")
      (node (ref "C13") (pin "1") (pinfunction "1_1") (pintype "passive"))
      (node (ref "R21") (pin "2") (pinfunction "2_2") (pintype "passive"))
      (node (ref "R29") (pin "1") (pinfunction "1_1") (pintype "passive"))
    )
    (net (code "52") (name "Net-(C14-Pad1)") (class "Default")
      (node (ref "C14") (pin "1") (pinfunction "1_1") (pintype "passive"))
      (node (ref "R22") (pin "2") (pinfunction "2_2") (pintype "passive"))
      (node (ref "R30") (pin "1") (pinfunction "1_1") (pintype "passive"))
    )
    (net (code "53") (name "Net-(C15-Pad1)") (class "Default")
      (node (ref "C15") (pin "1") (pinfunction "1_1") (pintype "passive"))
      (node (ref "R23") (pin "2") (pinfunction "2_2") (pintype "passive"))
      (node (ref "R31") (pin "1") (pinfunction "1_1") (pintype "passive"))
    )
    (net (code "54") (name "Net-(C16-Pad1)") (class "Default")
      (node (ref "C16") (pin "1") (pinfunction "1_1") (pintype "passive"))
      (node (ref "R24") (pin "2") (pinfunction "2_2") (pintype "passive"))
      (node (ref "R32") (pin "1") (pinfunction "1_1") (pintype "passive"))
    )
    (net (code "55") (name "Net-(C17-Pad1)") (class "Default")
      (node (ref "C17") (pin "1") (pinfunction "1_1") (pintype "passive"))
      (node (ref "R49") (pin "2") (pinfunction "2_2") (pintype "passive"))
      (node (ref "R50") (pin "1") (pinfunction "1_1") (pintype "passive"))
    )
    (net (code "56") (name "unconnected-(P1-Pad1)") (class "Default")
      (node (ref "P1") (pin "1") (pinfunction "1_1") (pintype "passive+no_connect"))
    )
    (net (code "57") (name "unconnected-(P1-Pad2)") (class "Default")
      (node (ref "P1") (pin "2") (pinfunction "2_2") (pintype "passive+no_connect"))
    )
    (net (code "58") (name "unconnected-(P1-Pad5)") (class "Default")
      (node (ref "P1") (pin "5") (pinfunction "5_5") (pintype "passive+no_connect"))
    )
    (net (code "59") (name "unconnected-(P1-Pad39)") (class "Default")
      (node (ref "P1") (pin "39") (pinfunction "39_39") (pintype "passive+no_connect"))
    )
    (net (code "60") (name "unconnected-(P1-Pad40)") (class "Default")
      (node (ref "P1") (pin "40") (pinfunction "40_40") (pintype "passive+no_connect"))
    )
  )
)
